# Sheet4.net
KiCad netlist of a schematic drawn in Altium Designer
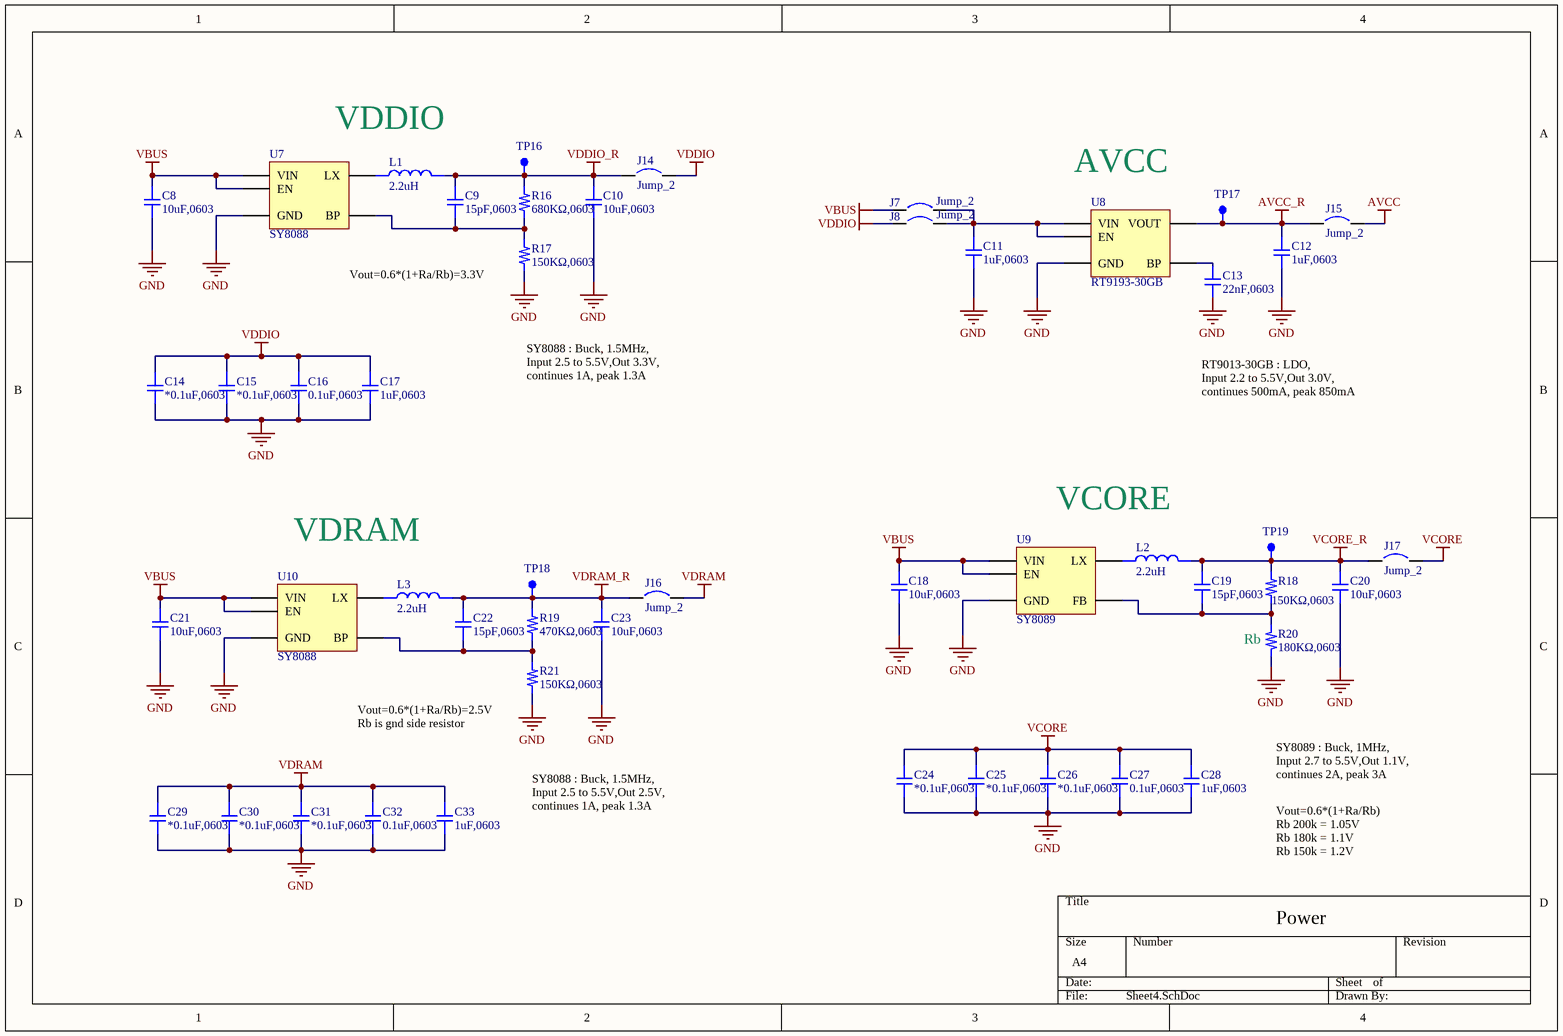
[diagram p0: Sheet4.SchDoc]

(export (version "E")
  (design (tool "Eeschema 10.0.6"))
  (components
    (comp (ref "C8") (value "10uF,0603") (footprint "C0603") (libsource (lib "myLib1") (part "Cap")))
    (comp (ref "C9") (value "15pF,0603") (footprint "C0603") (libsource (lib "myLib1") (part "Cap")))
    (comp (ref "C10") (value "10uF,0603") (footprint "C0603") (libsource (lib "myLib1") (part "Cap")))
    (comp (ref "C11") (value "1uF,0603") (footprint "C0603") (libsource (lib "myLib1") (part "Cap")))
    (comp (ref "C12") (value "1uF,0603") (footprint "C0603") (libsource (lib "myLib1") (part "Cap")))
    (comp (ref "C13") (value "22nF,0603") (footprint "C0603") (libsource (lib "myLib1") (part "Cap")))
    (comp (ref "C14") (value "*0.1uF,0603") (footprint "C0603") (libsource (lib "myLib1") (part "Cap")))
    (comp (ref "C15") (value "*0.1uF,0603") (footprint "C0603") (libsource (lib "myLib1") (part "Cap")))
    (comp (ref "C16") (value "0.1uF,0603") (footprint "C0603") (libsource (lib "myLib1") (part "Cap")))
    (comp (ref "C17") (value "1uF,0603") (footprint "C0603") (libsource (lib "myLib1") (part "Cap")))
    (comp (ref "C18") (value "10uF,0603") (footprint "C0603") (libsource (lib "myLib1") (part "Cap")))
    (comp (ref "C19") (value "15pF,0603") (footprint "C0603") (libsource (lib "myLib1") (part "Cap")))
    (comp (ref "C20") (value "10uF,0603") (footprint "C0603") (libsource (lib "myLib1") (part "Cap")))
    (comp (ref "C21") (value "10uF,0603") (footprint "C0603") (libsource (lib "myLib1") (part "Cap")))
    (comp (ref "C22") (value "15pF,0603") (footprint "C0603") (libsource (lib "myLib1") (part "Cap")))
    (comp (ref "C23") (value "10uF,0603") (footprint "C0603") (libsource (lib "myLib1") (part "Cap")))
    (comp (ref "C24") (value "*0.1uF,0603") (footprint "C0603") (libsource (lib "myLib1") (part "Cap")))
    (comp (ref "C25") (value "*0.1uF,0603") (footprint "C0603") (libsource (lib "myLib1") (part "Cap")))
    (comp (ref "C26") (value "*0.1uF,0603") (footprint "C0603") (libsource (lib "myLib1") (part "Cap")))
    (comp (ref "C27") (value "0.1uF,0603") (footprint "C0603") (libsource (lib "myLib1") (part "Cap")))
    (comp (ref "C28") (value "1uF,0603") (footprint "C0603") (libsource (lib "myLib1") (part "Cap")))
    (comp (ref "C29") (value "*0.1uF,0603") (footprint "C0603") (libsource (lib "myLib1") (part "Cap")))
    (comp (ref "C30") (value "*0.1uF,0603") (footprint "C0603") (libsource (lib "myLib1") (part "Cap")))
    (comp (ref "C31") (value "*0.1uF,0603") (footprint "C0603") (libsource (lib "myLib1") (part "Cap")))
    (comp (ref "C32") (value "0.1uF,0603") (footprint "C0603") (libsource (lib "myLib1") (part "Cap")))
    (comp (ref "C33") (value "1uF,0603") (footprint "C0603") (libsource (lib "myLib1") (part "Cap")))
    (comp (ref "J7") (value "Jump_2") (footprint "Jp_small") (libsource (lib "myLib1") (part "Jump_2")))
    (comp (ref "J8") (value "Jump_2") (footprint "Jp_small") (libsource (lib "myLib1") (part "Jump_2")))
    (comp (ref "J14") (value "Jump_2") (footprint "power_jump") (libsource (lib "myLib1") (part "Jump_2")))
    (comp (ref "J15") (value "Jump_2") (footprint "power_jump") (libsource (lib "myLib1") (part "Jump_2")))
    (comp (ref "J16") (value "Jump_2") (footprint "power_jump") (libsource (lib "myLib1") (part "Jump_2")))
    (comp (ref "J17") (value "Jump_2") (footprint "power_jump") (libsource (lib "myLib1") (part "Jump_2")))
    (comp (ref "L1") (value "2.2uH") (footprint "IND_252010_SMD") (libsource (lib "myLib1") (part "Ind")))
    (comp (ref "L2") (value "2.2uH") (footprint "IND_252010_SMD") (libsource (lib "myLib1") (part "Ind")))
    (comp (ref "L3") (value "2.2uH") (footprint "IND_252010_SMD") (libsource (lib "myLib1") (part "Ind")))
    (comp (ref "R16") (value "680KΩ,0603") (footprint "R0603") (libsource (lib "myLib1") (part "Res")))
    (comp (ref "R17") (value "150KΩ,0603") (footprint "R0603") (libsource (lib "myLib1") (part "Res")))
    (comp (ref "R18") (value "150KΩ,0603") (footprint "R0603") (libsource (lib "myLib1") (part "Res")))
    (comp (ref "R19") (value "470KΩ,0603") (footprint "R0603") (libsource (lib "myLib1") (part "Res")))
    (comp (ref "R20") (value "180KΩ,0603") (footprint "R0603") (libsource (lib "myLib1") (part "Res")))
    (comp (ref "R21") (value "150KΩ,0603") (footprint "R0603") (libsource (lib "myLib1") (part "Res")))
    (comp (ref "TP16") (value "TP") (footprint "TP") (libsource (lib "myLib1") (part "TP")))
    (comp (ref "TP17") (value "TP") (footprint "TP") (libsource (lib "myLib1") (part "TP")))
    (comp (ref "TP18") (value "TP") (footprint "TP") (libsource (lib "myLib1") (part "TP")))
    (comp (ref "TP19") (value "TP") (footprint "TP") (libsource (lib "myLib1") (part "TP")))
    (comp (ref "U7") (value "SY8088") (footprint "SOT-23-5p") (libsource (lib "myLib1") (part "SY8088")))
    (comp (ref "U8")
      (value "RT9193-30GB")
      (footprint "SOT-23-5p")
      (libsource (lib "myLib1") (part "RT9193-30GB"))
    )
    (comp (ref "U9") (value "SY8089") (footprint "SOT-23-5p") (libsource (lib "myLib1") (part "SY8089")))
    (comp (ref "U10") (value "SY8088") (footprint "SOT-23-5p") (libsource (lib "myLib1") (part "SY8088")))
  )
  (nets
    (net (code "1") (name "AVCC") (class "Default")
      (node (ref "J15") (pin "02") (pinfunction "2_02") (pintype "passive"))
    )
    (net (code "2") (name "AVCC_R") (class "Default")
      (node (ref "C12") (pin "02") (pintype "passive"))
      (node (ref "J15") (pin "01") (pinfunction "1_01") (pintype "passive"))
      (node (ref "TP17") (pin "01") (pintype "passive"))
      (node (ref "U8") (pin "05") (pinfunction "VOUT_05") (pintype "passive"))
    )
    (net (code "3") (name "GND") (class "Default")
      (node (ref "C10") (pin "01") (pintype "passive"))
      (node (ref "C11") (pin "02") (pintype "passive"))
      (node (ref "C12") (pin "01") (pintype "passive"))
      (node (ref "C13") (pin "01") (pintype "passive"))
      (node (ref "C14") (pin "01") (pintype "passive"))
      (node (ref "C15") (pin "01") (pintype "passive"))
      (node (ref "C16") (pin "01") (pintype "passive"))
      (node (ref "C17") (pin "01") (pintype "passive"))
      (node (ref "C18") (pin "02") (pintype "passive"))
      (node (ref "C20") (pin "01") (pintype "passive"))
      (node (ref "C21") (pin "02") (pintype "passive"))
      (node (ref "C23") (pin "01") (pintype "passive"))
      (node (ref "C24") (pin "01") (pintype "passive"))
      (node (ref "C25") (pin "01") (pintype "passive"))
      (node (ref "C26") (pin "01") (pintype "passive"))
      (node (ref "C27") (pin "01") (pintype "passive"))
      (node (ref "C28") (pin "01") (pintype "passive"))
      (node (ref "C29") (pin "01") (pintype "passive"))
      (node (ref "C30") (pin "01") (pintype "passive"))
      (node (ref "C31") (pin "01") (pintype "passive"))
      (node (ref "C32") (pin "01") (pintype "passive"))
      (node (ref "C33") (pin "01") (pintype "passive"))
      (node (ref "C8") (pin "02") (pintype "passive"))
      (node (ref "R17") (pin "01") (pintype "passive"))
      (node (ref "R20") (pin "01") (pintype "passive"))
      (node (ref "R21") (pin "01") (pintype "passive"))
      (node (ref "U10") (pin "02") (pinfunction "GND_02") (pintype "passive"))
      (node (ref "U7") (pin "02") (pinfunction "GND_02") (pintype "passive"))
      (node (ref "U8") (pin "02") (pinfunction "GND_02") (pintype "passive"))
      (node (ref "U9") (pin "02") (pinfunction "GND_02") (pintype "passive"))
    )
    (net (code "4") (name "Net-(J7-2)") (class "Default")
      (node (ref "C11") (pin "01") (pintype "passive"))
      (node (ref "J7") (pin "02") (pinfunction "2_02") (pintype "passive"))
      (node (ref "J8") (pin "02") (pinfunction "2_02") (pintype "passive"))
      (node (ref "U8") (pin "01") (pinfunction "VIN_01") (pintype "passive"))
      (node (ref "U8") (pin "03") (pinfunction "EN_03") (pintype "passive"))
    )
    (net (code "5") (name "Net-(U7-BP)") (class "Default")
      (node (ref "C9") (pin "01") (pintype "passive"))
      (node (ref "R16") (pin "01") (pintype "passive"))
      (node (ref "R17") (pin "02") (pintype "passive"))
      (node (ref "U7") (pin "05") (pinfunction "BP_05") (pintype "passive"))
    )
    (net (code "6") (name "Net-(U7-LX)") (class "Default")
      (node (ref "L1") (pin "01") (pinfunction "01_01") (pintype "passive"))
      (node (ref "U7") (pin "03") (pinfunction "LX_03") (pintype "passive"))
    )
    (net (code "7") (name "Net-(U8-BP)") (class "Default")
      (node (ref "C13") (pin "02") (pintype "passive"))
      (node (ref "U8") (pin "04") (pinfunction "BP_04") (pintype "passive"))
    )
    (net (code "8") (name "Net-(U9-FB)") (class "Default")
      (node (ref "C19") (pin "01") (pintype "passive"))
      (node (ref "R18") (pin "01") (pintype "passive"))
      (node (ref "R20") (pin "02") (pintype "passive"))
      (node (ref "U9") (pin "05") (pinfunction "FB_05") (pintype "passive"))
    )
    (net (code "9") (name "Net-(U9-LX)") (class "Default")
      (node (ref "L2") (pin "01") (pinfunction "01_01") (pintype "passive"))
      (node (ref "U9") (pin "03") (pinfunction "LX_03") (pintype "passive"))
    )
    (net (code "10") (name "Net-(U10-BP)") (class "Default")
      (node (ref "C22") (pin "01") (pintype "passive"))
      (node (ref "R19") (pin "01") (pintype "passive"))
      (node (ref "R21") (pin "02") (pintype "passive"))
      (node (ref "U10") (pin "05") (pinfunction "BP_05") (pintype "passive"))
    )
    (net (code "11") (name "Net-(U10-LX)") (class "Default")
      (node (ref "L3") (pin "01") (pinfunction "01_01") (pintype "passive"))
      (node (ref "U10") (pin "03") (pinfunction "LX_03") (pintype "passive"))
    )
    (net (code "12") (name "VBUS") (class "Default")
      (node (ref "C18") (pin "01") (pintype "passive"))
      (node (ref "C21") (pin "01") (pintype "passive"))
      (node (ref "C8") (pin "01") (pintype "passive"))
      (node (ref "J7") (pin "01") (pinfunction "1_01") (pintype "passive"))
      (node (ref "U10") (pin "01") (pinfunction "EN_01") (pintype "passive"))
      (node (ref "U10") (pin "04") (pinfunction "VIN_04") (pintype "passive"))
      (node (ref "U7") (pin "01") (pinfunction "EN_01") (pintype "passive"))
      (node (ref "U7") (pin "04") (pinfunction "VIN_04") (pintype "passive"))
      (node (ref "U9") (pin "01") (pinfunction "EN_01") (pintype "passive"))
      (node (ref "U9") (pin "04") (pinfunction "VIN_04") (pintype "passive"))
    )
    (net (code "13") (name "VCORE") (class "Default")
      (node (ref "C24") (pin "02") (pintype "passive"))
      (node (ref "C25") (pin "02") (pintype "passive"))
      (node (ref "C26") (pin "02") (pintype "passive"))
      (node (ref "C27") (pin "02") (pintype "passive"))
      (node (ref "C28") (pin "02") (pintype "passive"))
      (node (ref "J17") (pin "02") (pinfunction "2_02") (pintype "passive"))
    )
    (net (code "14") (name "VCORE_R") (class "Default")
      (node (ref "C19") (pin "02") (pintype "passive"))
      (node (ref "C20") (pin "02") (pintype "passive"))
      (node (ref "J17") (pin "01") (pinfunction "1_01") (pintype "passive"))
      (node (ref "L2") (pin "02") (pinfunction "02_02") (pintype "passive"))
      (node (ref "R18") (pin "02") (pintype "passive"))
      (node (ref "TP19") (pin "01") (pintype "passive"))
    )
    (net (code "15") (name "VDDIO") (class "Default")
      (node (ref "C14") (pin "02") (pintype "passive"))
      (node (ref "C15") (pin "02") (pintype "passive"))
      (node (ref "C16") (pin "02") (pintype "passive"))
      (node (ref "C17") (pin "02") (pintype "passive"))
      (node (ref "J14") (pin "02") (pinfunction "2_02") (pintype "passive"))
      (node (ref "J8") (pin "01") (pinfunction "1_01") (pintype "passive"))
    )
    (net (code "16") (name "VDDIO_R") (class "Default")
      (node (ref "C10") (pin "02") (pintype "passive"))
      (node (ref "C9") (pin "02") (pintype "passive"))
      (node (ref "J14") (pin "01") (pinfunction "1_01") (pintype "passive"))
      (node (ref "L1") (pin "02") (pinfunction "02_02") (pintype "passive"))
      (node (ref "R16") (pin "02") (pintype "passive"))
      (node (ref "TP16") (pin "01") (pintype "passive"))
    )
    (net (code "17") (name "VDRAM") (class "Default")
      (node (ref "C29") (pin "02") (pintype "passive"))
      (node (ref "C30") (pin "02") (pintype "passive"))
      (node (ref "C31") (pin "02") (pintype "passive"))
      (node (ref "C32") (pin "02") (pintype "passive"))
      (node (ref "C33") (pin "02") (pintype "passive"))
      (node (ref "J16") (pin "02") (pinfunction "2_02") (pintype "passive"))
    )
    (net (code "18") (name "VDRAM_R") (class "Default")
      (node (ref "C22") (pin "02") (pintype "passive"))
      (node (ref "C23") (pin "02") (pintype "passive"))
      (node (ref "J16") (pin "01") (pinfunction "1_01") (pintype "passive"))
      (node (ref "L3") (pin "02") (pinfunction "02_02") (pintype "passive"))
      (node (ref "R19") (pin "02") (pintype "passive"))
      (node (ref "TP18") (pin "01") (pintype "passive"))
    )
  )
)
